# Blinds_Driver.net
KiCad netlist of a schematic drawn in EAGLE
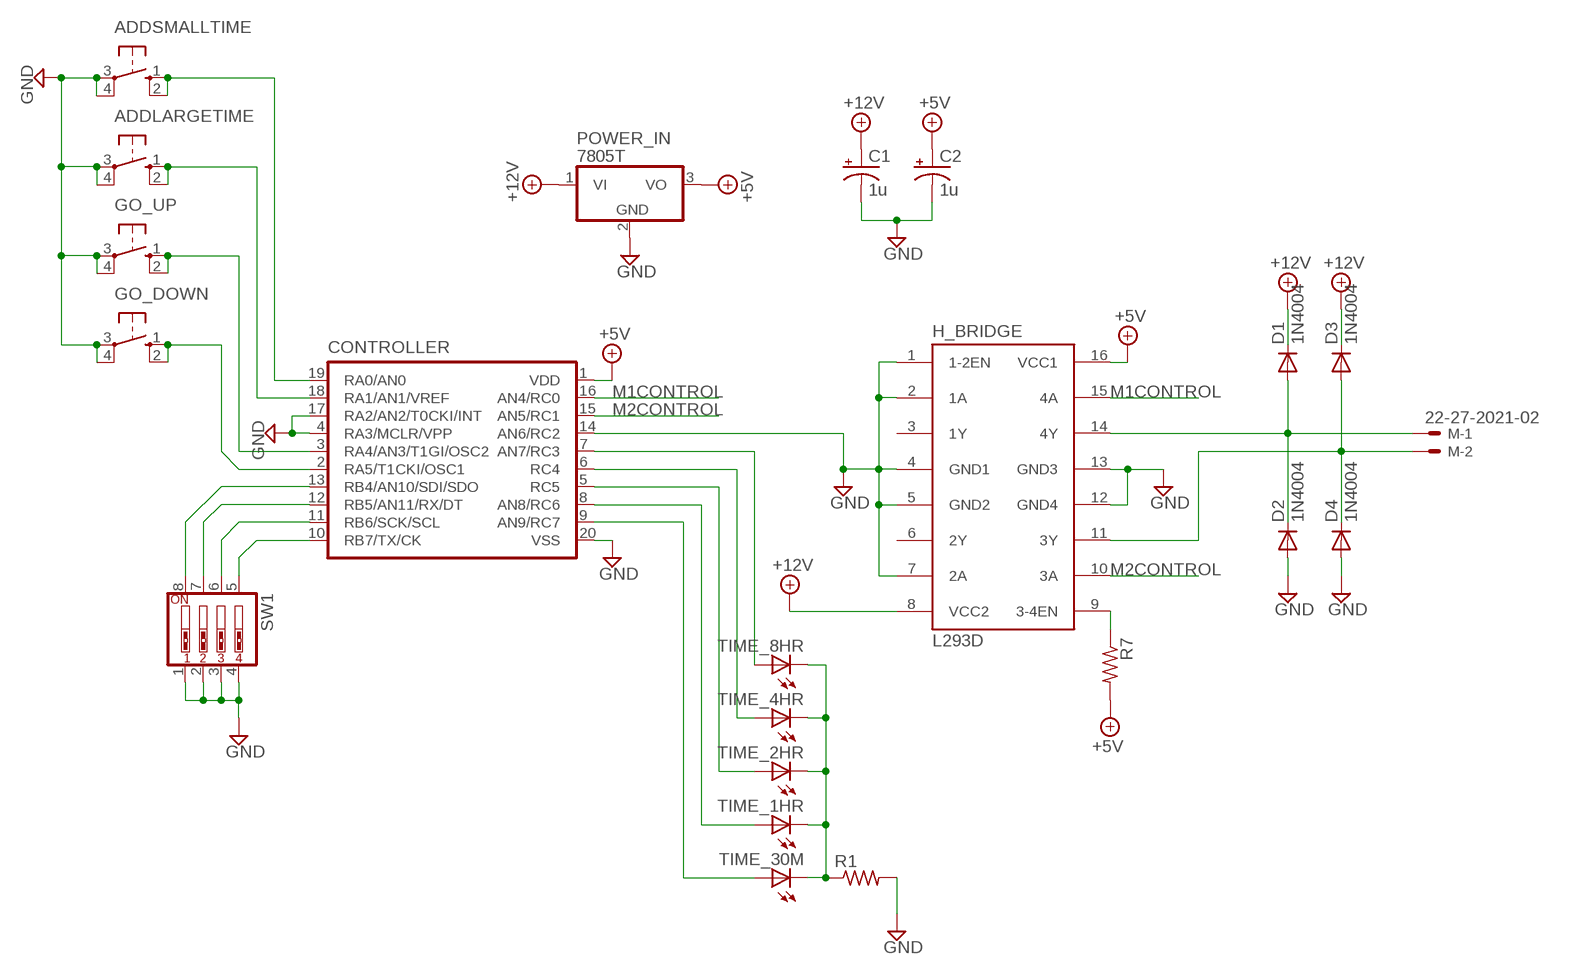
[diagram p0: schematic, sheet 1]

(export (version "E")
  (design (tool "Eeschema 10.0.6"))
  (components
    (comp (ref "ADDLARGETIME")
      (value "10-XX")
      (footprint "eagle-import:B3F-10XX")
      (fields (field (name "MPN") "B3F-1000"))
      (libsource (lib "eagle-import") (part "10-XX"))
    )
    (comp (ref "ADDSMALLTIME")
      (value "10-XX")
      (footprint "eagle-import:B3F-10XX")
      (fields (field (name "MPN") "B3F-1000"))
      (libsource (lib "eagle-import") (part "10-XX"))
    )
    (comp (ref "C1")
      (value "1u")
      (footprint "eagle-import:E2,5-6E")
      (libsource (lib "eagle-import") (part "CPOL-USE2,5-6E"))
    )
    (comp (ref "C2")
      (value "1u")
      (footprint "eagle-import:E2,5-6E")
      (libsource (lib "eagle-import") (part "CPOL-USE2,5-6E"))
    )
    (comp (ref "CONTROLLER")
      (value "PIC16F6XX")
      (footprint "eagle-import:DIL20")
      (libsource (lib "eagle-import") (part "PIC16F6XX"))
    )
    (comp (ref "D1")
      (value "1N4004")
      (footprint "eagle-import:DO41-10")
      (libsource (lib "eagle-import") (part "1N4004"))
    )
    (comp (ref "D2")
      (value "1N4004")
      (footprint "eagle-import:DO41-10")
      (libsource (lib "eagle-import") (part "1N4004"))
    )
    (comp (ref "D3")
      (value "1N4004")
      (footprint "eagle-import:DO41-10")
      (libsource (lib "eagle-import") (part "1N4004"))
    )
    (comp (ref "D4")
      (value "1N4004")
      (footprint "eagle-import:DO41-10")
      (libsource (lib "eagle-import") (part "1N4004"))
    )
    (comp (ref "GO_DOWN")
      (value "10-XX")
      (footprint "eagle-import:B3F-10XX")
      (fields (field (name "MPN") "B3F-1000"))
      (libsource (lib "eagle-import") (part "10-XX"))
    )
    (comp (ref "GO_UP")
      (value "10-XX")
      (footprint "eagle-import:B3F-10XX")
      (fields (field (name "MPN") "B3F-1000"))
      (libsource (lib "eagle-import") (part "10-XX"))
    )
    (comp (ref "H_BRIDGE")
      (value "L293D")
      (footprint "eagle-import:DIL16")
      (libsource (lib "eagle-import") (part "L293D"))
    )
    (comp (ref "M")
      (value "22-27-2021-02")
      (footprint "eagle-import:6410-02")
      (libsource (lib "eagle-import") (part "22-?-0227-2021"))
    )
    (comp (ref "POWER_IN")
      (value "7805T")
      (footprint "eagle-import:TO220H")
      (libsource (lib "eagle-import") (part "78T05"))
    )
    (comp (ref "R1")
      (value "R-US_0207/10")
      (footprint "eagle-import:0207_10")
      (libsource (lib "eagle-import") (part "R-US_0207/10"))
    )
    (comp (ref "R7")
      (value "R-US_0207/10")
      (footprint "eagle-import:0207_10")
      (libsource (lib "eagle-import") (part "R-US_0207/10"))
    )
    (comp (ref "SW1")
      (value "SW_DIP-4")
      (footprint "eagle-import:EDG-04")
      (libsource (lib "eagle-import") (part "SW_DIP-4"))
    )
    (comp (ref "TIME_1HR")
      (value "LED5MM")
      (footprint "eagle-import:LED5MM")
      (libsource (lib "eagle-import") (part "LED5MM"))
    )
    (comp (ref "TIME_2HR")
      (value "LED5MM")
      (footprint "eagle-import:LED5MM")
      (libsource (lib "eagle-import") (part "LED5MM"))
    )
    (comp (ref "TIME_4HR")
      (value "LED5MM")
      (footprint "eagle-import:LED5MM")
      (libsource (lib "eagle-import") (part "LED5MM"))
    )
    (comp (ref "TIME_8HR")
      (value "LED5MM")
      (footprint "eagle-import:LED5MM")
      (libsource (lib "eagle-import") (part "LED5MM"))
    )
    (comp (ref "TIME_30M")
      (value "LED5MM")
      (footprint "eagle-import:LED5MM")
      (libsource (lib "eagle-import") (part "LED5MM"))
    )
  )
  (nets
    (net (code "1") (name "+5V") (class "Default")
      (node (ref "C2") (pin "+") (pinfunction "+_+") (pintype "passive"))
      (node (ref "CONTROLLER") (pin "1") (pinfunction "VDD_1") (pintype "power_in"))
      (node (ref "H_BRIDGE") (pin "16") (pinfunction "VCC1_16") (pintype "power_in"))
      (node (ref "POWER_IN") (pin "3") (pinfunction "VO_3") (pintype "passive"))
      (node (ref "R7") (pin "2") (pinfunction "2_2") (pintype "passive"))
    )
    (net (code "2") (name "+12V") (class "Default")
      (node (ref "C1") (pin "+") (pinfunction "+_+") (pintype "passive"))
      (node (ref "D1") (pin "C") (pinfunction "C_C") (pintype "passive"))
      (node (ref "D3") (pin "C") (pinfunction "C_C") (pintype "passive"))
      (node (ref "H_BRIDGE") (pin "8") (pinfunction "VCC2_8") (pintype "power_in"))
      (node (ref "POWER_IN") (pin "1") (pinfunction "VI_1") (pintype "input"))
    )
    (net (code "3") (name "/M1CONTROL") (class "Default")
      (node (ref "CONTROLLER") (pin "16") (pinfunction "AN4/RC0_16") (pintype "bidirectional"))
      (node (ref "H_BRIDGE") (pin "15") (pinfunction "4A_15") (pintype "input"))
    )
    (net (code "4") (name "/M2CONTROL") (class "Default")
      (node (ref "CONTROLLER") (pin "15") (pinfunction "AN5/RC1_15") (pintype "bidirectional"))
      (node (ref "H_BRIDGE") (pin "10") (pinfunction "3A_10") (pintype "input"))
    )
    (net (code "5") (name "GND") (class "Default")
      (node (ref "ADDLARGETIME") (pin "3") (pinfunction "P_3") (pintype "passive"))
      (node (ref "ADDLARGETIME") (pin "4") (pinfunction "P1_4") (pintype "passive"))
      (node (ref "ADDSMALLTIME") (pin "3") (pinfunction "P_3") (pintype "passive"))
      (node (ref "ADDSMALLTIME") (pin "4") (pinfunction "P1_4") (pintype "passive"))
      (node (ref "C1") (pin "-") (pinfunction "-_-") (pintype "passive"))
      (node (ref "C2") (pin "-") (pinfunction "-_-") (pintype "passive"))
      (node (ref "CONTROLLER") (pin "14") (pinfunction "AN6/RC2_14") (pintype "bidirectional"))
      (node (ref "CONTROLLER") (pin "17") (pinfunction "RA2/AN2/T0CKI/INT_17") (pintype "bidirectional"))
      (node (ref "CONTROLLER") (pin "20") (pinfunction "VSS_20") (pintype "power_in"))
      (node (ref "CONTROLLER") (pin "4") (pinfunction "RA3/MCLR/VPP_4") (pintype "input"))
      (node (ref "D2") (pin "A") (pinfunction "A_A") (pintype "passive"))
      (node (ref "D4") (pin "A") (pinfunction "A_A") (pintype "passive"))
      (node (ref "GO_DOWN") (pin "3") (pinfunction "P_3") (pintype "passive"))
      (node (ref "GO_DOWN") (pin "4") (pinfunction "P1_4") (pintype "passive"))
      (node (ref "GO_UP") (pin "3") (pinfunction "P_3") (pintype "passive"))
      (node (ref "GO_UP") (pin "4") (pinfunction "P1_4") (pintype "passive"))
      (node (ref "H_BRIDGE") (pin "1") (pinfunction "1-2EN_1") (pintype "input"))
      (node (ref "H_BRIDGE") (pin "12") (pinfunction "GND4_12") (pintype "power_in"))
      (node (ref "H_BRIDGE") (pin "13") (pinfunction "GND3_13") (pintype "power_in"))
      (node (ref "H_BRIDGE") (pin "2") (pinfunction "1A_2") (pintype "input"))
      (node (ref "H_BRIDGE") (pin "4") (pinfunction "GND1_4") (pintype "power_in"))
      (node (ref "H_BRIDGE") (pin "5") (pinfunction "GND2_5") (pintype "power_in"))
      (node (ref "H_BRIDGE") (pin "7") (pinfunction "2A_7") (pintype "input"))
      (node (ref "POWER_IN") (pin "2") (pinfunction "GND_2") (pintype "passive"))
      (node (ref "R1") (pin "2") (pinfunction "2_2") (pintype "passive"))
      (node (ref "SW1") (pin "1") (pinfunction "1_1") (pintype "passive"))
      (node (ref "SW1") (pin "2") (pinfunction "2_2") (pintype "passive"))
      (node (ref "SW1") (pin "3") (pinfunction "3_3") (pintype "passive"))
      (node (ref "SW1") (pin "4") (pinfunction "4_4") (pintype "passive"))
    )
    (net (code "6") (name "Net-(ADDLARGETIME-S)") (class "Default")
      (node (ref "ADDLARGETIME") (pin "1") (pinfunction "S_1") (pintype "passive"))
      (node (ref "ADDLARGETIME") (pin "2") (pinfunction "S1_2") (pintype "passive"))
      (node (ref "CONTROLLER") (pin "18") (pinfunction "RA1/AN1/VREF_18") (pintype "bidirectional"))
    )
    (net (code "7") (name "Net-(ADDSMALLTIME-S)") (class "Default")
      (node (ref "ADDSMALLTIME") (pin "1") (pinfunction "S_1") (pintype "passive"))
      (node (ref "ADDSMALLTIME") (pin "2") (pinfunction "S1_2") (pintype "passive"))
      (node (ref "CONTROLLER") (pin "19") (pinfunction "RA0/AN0_19") (pintype "bidirectional"))
    )
    (net (code "8") (name "Net-(CONTROLLER-AN7{slash}RC3)") (class "Default")
      (node (ref "CONTROLLER") (pin "7") (pinfunction "AN7/RC3_7") (pintype "bidirectional"))
      (node (ref "TIME_8HR") (pin "A") (pinfunction "A_A") (pintype "passive"))
    )
    (net (code "9") (name "Net-(CONTROLLER-AN8{slash}RC6)") (class "Default")
      (node (ref "CONTROLLER") (pin "8") (pinfunction "AN8/RC6_8") (pintype "bidirectional"))
      (node (ref "TIME_1HR") (pin "A") (pinfunction "A_A") (pintype "passive"))
    )
    (net (code "10") (name "Net-(CONTROLLER-AN9{slash}RC7)") (class "Default")
      (node (ref "CONTROLLER") (pin "9") (pinfunction "AN9/RC7_9") (pintype "bidirectional"))
      (node (ref "TIME_30M") (pin "A") (pinfunction "A_A") (pintype "passive"))
    )
    (net (code "11") (name "Net-(CONTROLLER-RA4{slash}AN3{slash}T1GI{slash}OSC2)") (class "Default")
      (node (ref "CONTROLLER") (pin "3") (pinfunction "RA4/AN3/T1GI/OSC2_3") (pintype "bidirectional"))
      (node (ref "GO_UP") (pin "1") (pinfunction "S_1") (pintype "passive"))
      (node (ref "GO_UP") (pin "2") (pinfunction "S1_2") (pintype "passive"))
    )
    (net (code "12") (name "Net-(CONTROLLER-RA5{slash}T1CKI{slash}OSC1)") (class "Default")
      (node (ref "CONTROLLER") (pin "2") (pinfunction "RA5/T1CKI/OSC1_2") (pintype "bidirectional"))
      (node (ref "GO_DOWN") (pin "1") (pinfunction "S_1") (pintype "passive"))
      (node (ref "GO_DOWN") (pin "2") (pinfunction "S1_2") (pintype "passive"))
    )
    (net (code "13") (name "Net-(CONTROLLER-RB4{slash}AN10{slash}SDI{slash}SDO)") (class "Default")
      (node (ref "CONTROLLER") (pin "13") (pinfunction "RB4/AN10/SDI/SDO_13") (pintype "bidirectional"))
      (node (ref "SW1") (pin "8") (pinfunction "8_8") (pintype "passive"))
    )
    (net (code "14") (name "Net-(CONTROLLER-RB5{slash}AN11{slash}RX{slash}DT)") (class "Default")
      (node (ref "CONTROLLER") (pin "12") (pinfunction "RB5/AN11/RX/DT_12") (pintype "bidirectional"))
      (node (ref "SW1") (pin "7") (pinfunction "7_7") (pintype "passive"))
    )
    (net (code "15") (name "Net-(CONTROLLER-RB6{slash}SCK{slash}SCL)") (class "Default")
      (node (ref "CONTROLLER") (pin "11") (pinfunction "RB6/SCK/SCL_11") (pintype "bidirectional"))
      (node (ref "SW1") (pin "6") (pinfunction "6_6") (pintype "passive"))
    )
    (net (code "16") (name "Net-(CONTROLLER-RB7{slash}TX{slash}CK)") (class "Default")
      (node (ref "CONTROLLER") (pin "10") (pinfunction "RB7/TX/CK_10") (pintype "bidirectional"))
      (node (ref "SW1") (pin "5") (pinfunction "5_5") (pintype "passive"))
    )
    (net (code "17") (name "Net-(CONTROLLER-RC4)") (class "Default")
      (node (ref "CONTROLLER") (pin "6") (pinfunction "RC4_6") (pintype "bidirectional"))
      (node (ref "TIME_4HR") (pin "A") (pinfunction "A_A") (pintype "passive"))
    )
    (net (code "18") (name "Net-(CONTROLLER-RC5)") (class "Default")
      (node (ref "CONTROLLER") (pin "5") (pinfunction "RC5_5") (pintype "bidirectional"))
      (node (ref "TIME_2HR") (pin "A") (pinfunction "A_A") (pintype "passive"))
    )
    (net (code "19") (name "Net-(H_BRIDGE-3-4EN)") (class "Default")
      (node (ref "H_BRIDGE") (pin "9") (pinfunction "3-4EN_9") (pintype "input"))
      (node (ref "R7") (pin "1") (pinfunction "1_1") (pintype "passive"))
    )
    (net (code "20") (name "Net-(H_BRIDGE-3Y)") (class "Default")
      (node (ref "D3") (pin "A") (pinfunction "A_A") (pintype "passive"))
      (node (ref "D4") (pin "C") (pinfunction "C_C") (pintype "passive"))
      (node (ref "H_BRIDGE") (pin "11") (pinfunction "3Y_11") (pintype "output"))
      (node (ref "M") (pin "2") (pinfunction "S_2") (pintype "passive"))
    )
    (net (code "21") (name "Net-(H_BRIDGE-4Y)") (class "Default")
      (node (ref "D1") (pin "A") (pinfunction "A_A") (pintype "passive"))
      (node (ref "D2") (pin "C") (pinfunction "C_C") (pintype "passive"))
      (node (ref "H_BRIDGE") (pin "14") (pinfunction "4Y_14") (pintype "output"))
      (node (ref "M") (pin "1") (pinfunction "S_1") (pintype "passive"))
    )
    (net (code "22") (name "Net-(TIME_1HR-C)") (class "Default")
      (node (ref "R1") (pin "1") (pinfunction "1_1") (pintype "passive"))
      (node (ref "TIME_1HR") (pin "K") (pinfunction "C_K") (pintype "passive"))
      (node (ref "TIME_2HR") (pin "K") (pinfunction "C_K") (pintype "passive"))
      (node (ref "TIME_30M") (pin "K") (pinfunction "C_K") (pintype "passive"))
      (node (ref "TIME_4HR") (pin "K") (pinfunction "C_K") (pintype "passive"))
      (node (ref "TIME_8HR") (pin "K") (pinfunction "C_K") (pintype "passive"))
    )
    (net (code "23") (name "unconnected-(H_BRIDGE-1Y-Pad3)") (class "Default")
      (node (ref "H_BRIDGE") (pin "3") (pinfunction "1Y_3") (pintype "output"))
    )
    (net (code "24") (name "unconnected-(H_BRIDGE-2Y-Pad6)") (class "Default")
      (node (ref "H_BRIDGE") (pin "6") (pinfunction "2Y_6") (pintype "output"))
    )
  )
)
